# myWatch.net
KiCad netlist of a schematic drawn in EAGLE
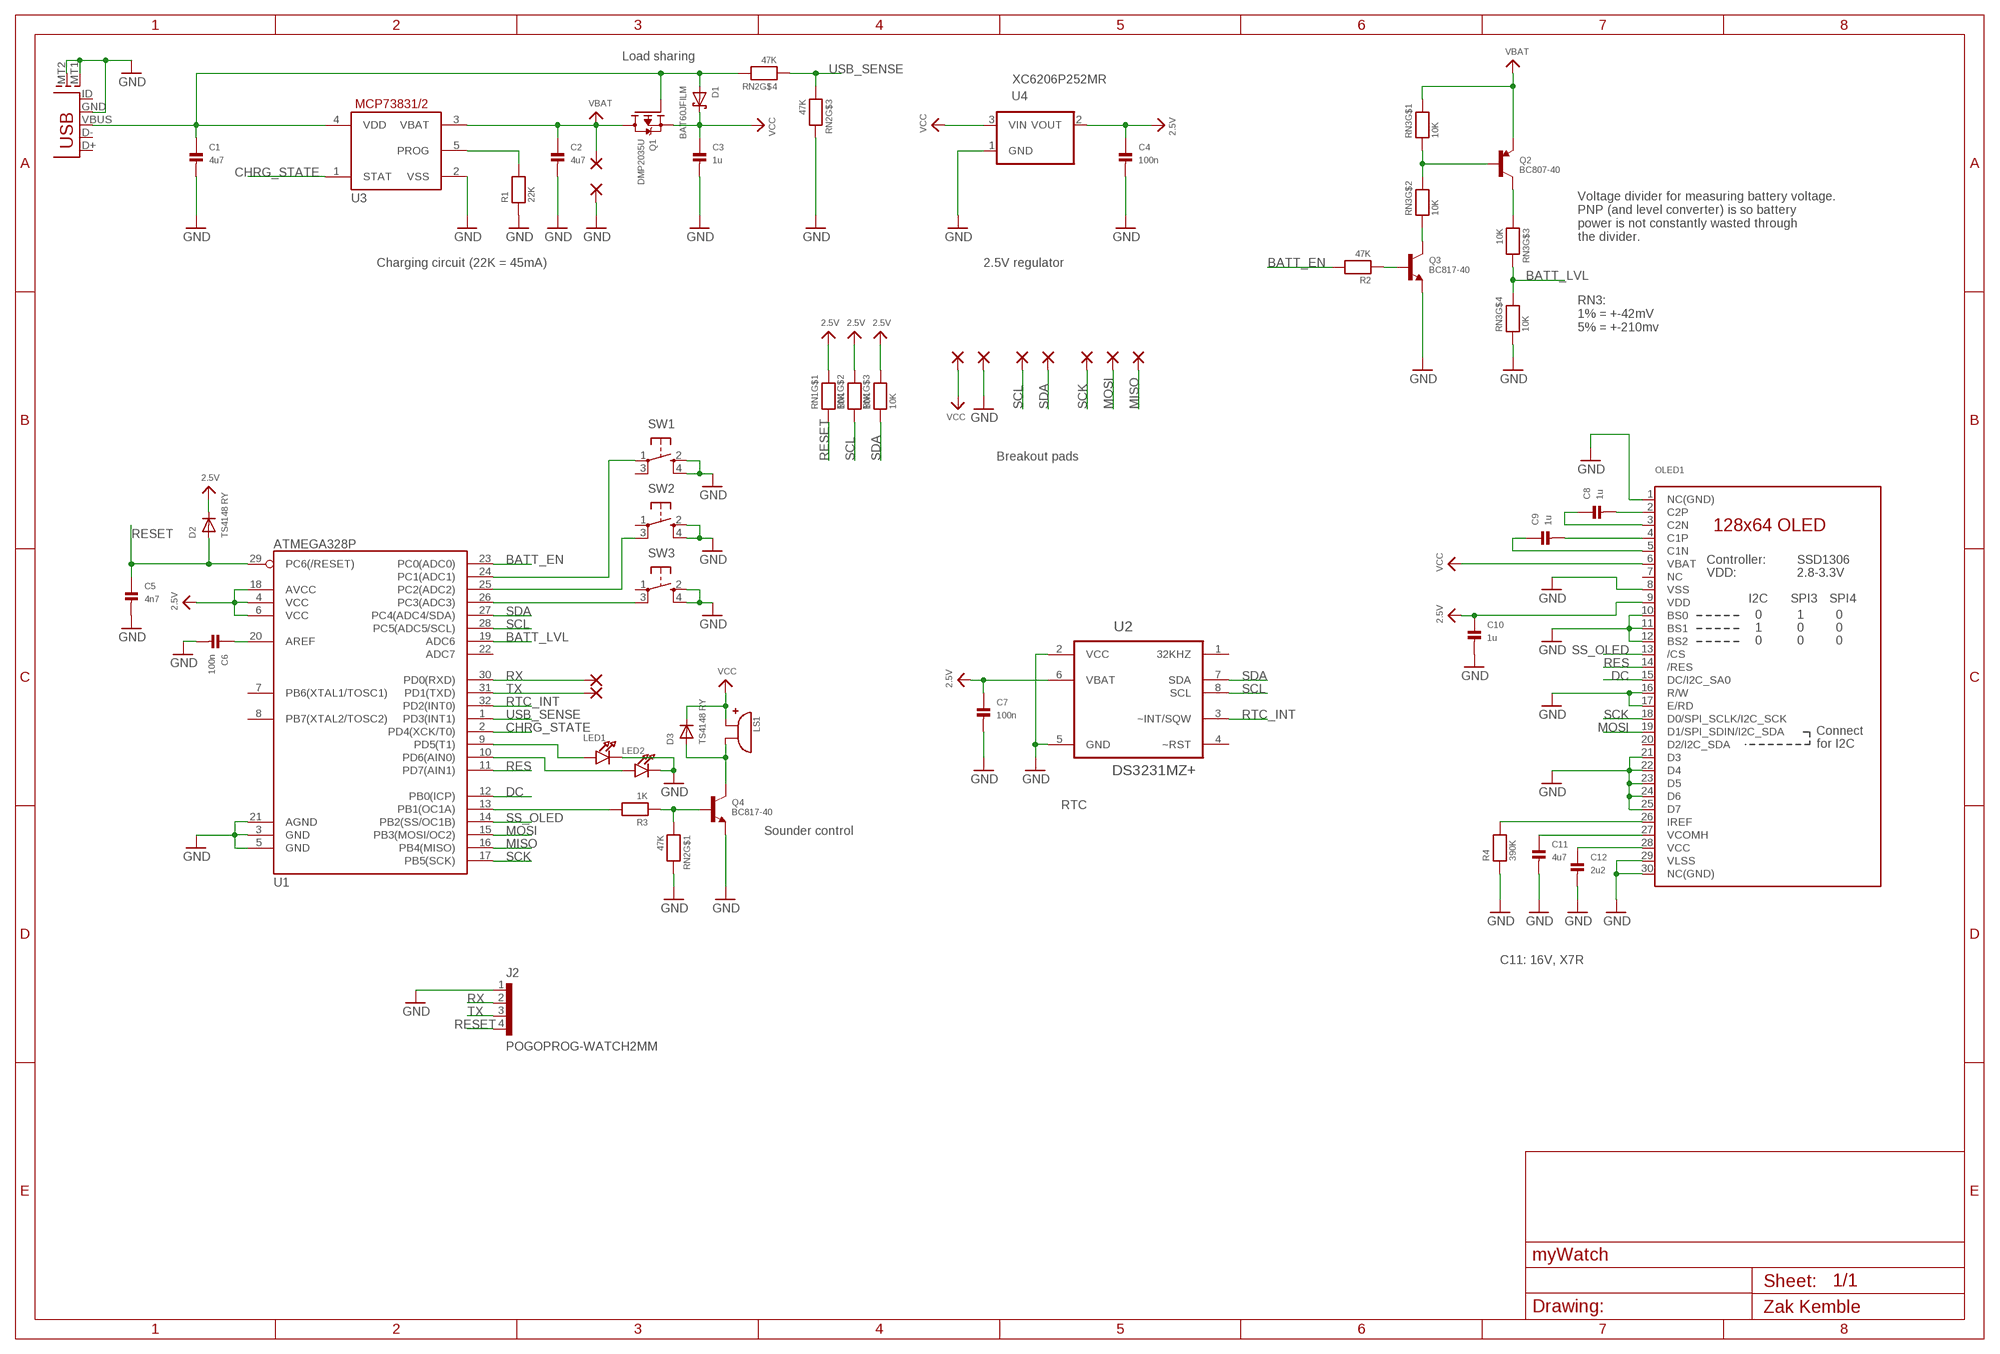
[diagram p0: schematic, sheet 1]

(export (version "E")
  (design (tool "Eeschema 10.0.6"))
  (components
    (comp (ref "C1")
      (value "4u7")
      (footprint "eagle-import:0805")
      (libsource (lib "eagle-import") (part "CAP_CERAMIC0805"))
    )
    (comp (ref "C2")
      (value "4u7")
      (footprint "eagle-import:0805")
      (libsource (lib "eagle-import") (part "CAP_CERAMIC0805"))
    )
    (comp (ref "C3")
      (value "1u")
      (footprint "eagle-import:0805")
      (libsource (lib "eagle-import") (part "CAP_CERAMIC0805"))
    )
    (comp (ref "C4")
      (value "100n")
      (footprint "eagle-import:_0402")
      (libsource (lib "eagle-import") (part "CAP_CERAMIC_0402"))
    )
    (comp (ref "C5")
      (value "4n7")
      (footprint "eagle-import:_0402")
      (libsource (lib "eagle-import") (part "CAP_CERAMIC_0402"))
    )
    (comp (ref "C6")
      (value "100n")
      (footprint "eagle-import:_0402")
      (libsource (lib "eagle-import") (part "CAP_CERAMIC_0402"))
    )
    (comp (ref "C7")
      (value "100n")
      (footprint "eagle-import:0805")
      (libsource (lib "eagle-import") (part "CAP_CERAMIC0805"))
    )
    (comp (ref "C8")
      (value "1u")
      (footprint "eagle-import:0805")
      (libsource (lib "eagle-import") (part "CAP_CERAMIC0805"))
    )
    (comp (ref "C9")
      (value "1u")
      (footprint "eagle-import:0805")
      (libsource (lib "eagle-import") (part "CAP_CERAMIC0805"))
    )
    (comp (ref "C10")
      (value "1u")
      (footprint "eagle-import:0805")
      (libsource (lib "eagle-import") (part "CAP_CERAMIC0805"))
    )
    (comp (ref "C11")
      (value "4u7")
      (footprint "eagle-import:0805")
      (libsource (lib "eagle-import") (part "CAP_CERAMIC0805"))
    )
    (comp (ref "C12")
      (value "2u2")
      (footprint "eagle-import:0805")
      (libsource (lib "eagle-import") (part "CAP_CERAMIC0805"))
    )
    (comp (ref "D1")
      (value "BAT60JFILM")
      (footprint "eagle-import:SOD-323")
      (libsource (lib "eagle-import") (part "DIODE-SCHOTTKYSOD-323"))
    )
    (comp (ref "D2")
      (value "TS4148 RY")
      (footprint "eagle-import:0805_DIODE")
      (libsource (lib "eagle-import") (part "DIODE_08050805"))
    )
    (comp (ref "D3")
      (value "TS4148 RY")
      (footprint "eagle-import:0805_DIODE")
      (libsource (lib "eagle-import") (part "DIODE_08050805"))
    )
    (comp (ref "J2")
      (value "POGOPROG-WATCH2MM")
      (footprint "eagle-import:POGOPROG_WATCH_2MM")
      (libsource (lib "eagle-import") (part "POGOPROG-WATCH2MM"))
    )
    (comp (ref "LED1")
      (value "LED0805")
      (footprint "eagle-import:CHIPLED_0805")
      (libsource (lib "eagle-import") (part "LED0805"))
    )
    (comp (ref "LED2")
      (value "LED0805")
      (footprint "eagle-import:CHIPLED_0805")
      (libsource (lib "eagle-import") (part "LED0805"))
    )
    (comp (ref "LS1")
      (value "ABMT-801-RC")
      (footprint "eagle-import:PIEZO")
      (libsource (lib "eagle-import") (part "ABMT-801-RC"))
    )
    (comp (ref "OLED1")
      (value "DISP_OLED_UG-2864HSWEG01_NOOUTLINEWATCH")
      (footprint "eagle-import:UG-2864HSWEG01_1.3_WRAPAROUND_WATCH")
      (libsource (lib "eagle-import") (part "DISP_OLED_UG-2864HSWEG01_NOOUTLINEWATCH"))
    )
    (comp (ref "PAD1")
      (value "SMD2")
      (footprint "eagle-import:SMD1,27-2,54")
      (libsource (lib "eagle-import") (part "SMD2"))
    )
    (comp (ref "PAD2")
      (value "SMD2")
      (footprint "eagle-import:SMD1,27-2,54")
      (libsource (lib "eagle-import") (part "SMD2"))
    )
    (comp (ref "PAD3")
      (value "SMD2")
      (footprint "eagle-import:SMD1,27-2,54")
      (libsource (lib "eagle-import") (part "SMD2"))
    )
    (comp (ref "PAD4")
      (value "SMD2")
      (footprint "eagle-import:SMD1,27-2,54")
      (libsource (lib "eagle-import") (part "SMD2"))
    )
    (comp (ref "PAD5")
      (value "SMD2")
      (footprint "eagle-import:SMD1,27-2,54")
      (libsource (lib "eagle-import") (part "SMD2"))
    )
    (comp (ref "PAD6")
      (value "SMD2")
      (footprint "eagle-import:SMD1,27-2,54")
      (libsource (lib "eagle-import") (part "SMD2"))
    )
    (comp (ref "PAD7")
      (value "SMD2")
      (footprint "eagle-import:SMD1,27-2,54")
      (libsource (lib "eagle-import") (part "SMD2"))
    )
    (comp (ref "PAD8")
      (value "SMD2")
      (footprint "eagle-import:SMD1,27-2,54")
      (libsource (lib "eagle-import") (part "SMD2"))
    )
    (comp (ref "PAD10")
      (value "SMD2")
      (footprint "eagle-import:SMD1,27-2,54")
      (libsource (lib "eagle-import") (part "SMD2"))
    )
    (comp (ref "PAD11")
      (value "SMD2")
      (footprint "eagle-import:SMD1,27-2,54")
      (libsource (lib "eagle-import") (part "SMD2"))
    )
    (comp (ref "PAD12")
      (value "SMD2")
      (footprint "eagle-import:SMD1,27-2,54")
      (libsource (lib "eagle-import") (part "SMD2"))
    )
    (comp (ref "Q1")
      (value "DMP2035U")
      (footprint "eagle-import:SOT23-WIDE")
      (libsource (lib "eagle-import") (part "MOSFET-PWIDE"))
    )
    (comp (ref "Q2")
      (value "BC807-40")
      (footprint "eagle-import:SOT23-WIDE")
      (libsource (lib "eagle-import") (part "TRANSISTOR_PNPWIDE"))
    )
    (comp (ref "Q3")
      (value "BC817-40")
      (footprint "eagle-import:SOT23-WIDE")
      (libsource (lib "eagle-import") (part "TRANSISTOR_NPNWIDE"))
    )
    (comp (ref "Q4")
      (value "BC817-40")
      (footprint "eagle-import:SOT23-WIDE")
      (libsource (lib "eagle-import") (part "TRANSISTOR_NPNWIDE"))
    )
    (comp (ref "R1")
      (value "22K")
      (footprint "eagle-import:_0402")
      (libsource (lib "eagle-import") (part "RESISTOR_0402"))
    )
    (comp (ref "R2")
      (value "47K")
      (footprint "eagle-import:_0402")
      (libsource (lib "eagle-import") (part "RESISTOR_0402"))
    )
    (comp (ref "R3")
      (value "1K")
      (footprint "eagle-import:_0402")
      (libsource (lib "eagle-import") (part "RESISTOR_0402"))
    )
    (comp (ref "R4")
      (value "390K")
      (footprint "eagle-import:0805")
      (libsource (lib "eagle-import") (part "RESISTOR0805"))
    )
    (comp (ref "RN1")
      (value "10K")
      (footprint "eagle-import:RESPACK_4X0603")
      (libsource (lib "eagle-import") (part "RESISTOR_4PACK"))
    )
    (comp (ref "RN2")
      (value "47K")
      (footprint "eagle-import:RESPACK_4X0603")
      (libsource (lib "eagle-import") (part "RESISTOR_4PACK"))
    )
    (comp (ref "RN3")
      (value "10K")
      (footprint "eagle-import:RESPACK_4X0603")
      (libsource (lib "eagle-import") (part "RESISTOR_4PACK"))
    )
    (comp (ref "SW1")
      (value "SPST_TACTRA")
      (footprint "eagle-import:TACT_SMD2")
      (libsource (lib "eagle-import") (part "SPST_TACTRA"))
    )
    (comp (ref "SW2")
      (value "SPST_TACTRA")
      (footprint "eagle-import:TACT_SMD2")
      (libsource (lib "eagle-import") (part "SPST_TACTRA"))
    )
    (comp (ref "SW3")
      (value "SPST_TACTRA")
      (footprint "eagle-import:TACT_SMD2")
      (libsource (lib "eagle-import") (part "SPST_TACTRA"))
    )
    (comp (ref "U1")
      (value "ATMEGA328P")
      (footprint "eagle-import:TQFP32-08")
      (libsource (lib "eagle-import") (part "ATMEGA328_SMT"))
    )
    (comp (ref "U2")
      (value "DS3231MZ+")
      (footprint "eagle-import:SOIC8_150MIL_SMPAD")
      (libsource (lib "eagle-import") (part "DS3231MZ+SMPAD"))
    )
    (comp (ref "U3")
      (value "MCP73832T-2ACI/OT")
      (footprint "eagle-import:SOT23-5L")
      (libsource (lib "eagle-import") (part "MCP73831/OT"))
    )
    (comp (ref "U4")
      (value "XC6206P252MR")
      (footprint "eagle-import:SOT-23")
      (libsource (lib "eagle-import") (part "MCP1700T-2502E/TTWIDE_PAD"))
    )
    (comp (ref "USB1")
      (value "USB-MICROBLARGEPAD")
      (footprint "eagle-import:USB-MICROB_LARGEPAD")
      (libsource (lib "eagle-import") (part "USB-MICROBLARGEPAD"))
    )
  )
  (nets
    (net (code "1") (name "/BATT_EN") (class "Default")
      (node (ref "R2") (pin "2") (pinfunction "2_2") (pintype "passive"))
      (node (ref "U1") (pin "23") (pinfunction "PC0(ADC0)_23") (pintype "bidirectional"))
    )
    (net (code "2") (name "/BATT_LVL") (class "Default")
      (node (ref "RN3") (pin "5") (pinfunction "2_5") (pintype "passive"))
      (node (ref "RN3") (pin "6") (pinfunction "2_6") (pintype "passive"))
      (node (ref "U1") (pin "19") (pinfunction "ADC6_19") (pintype "bidirectional"))
    )
    (net (code "3") (name "/CHRG_STATE") (class "Default")
      (node (ref "U1") (pin "2") (pinfunction "PD4(XCK/T0)_2") (pintype "bidirectional"))
      (node (ref "U3") (pin "1") (pinfunction "STAT_1") (pintype "output"))
    )
    (net (code "4") (name "/DC") (class "Default")
      (node (ref "OLED1") (pin "15") (pinfunction "DC/I2C_SA0_15") (pintype "input"))
      (node (ref "U1") (pin "12") (pinfunction "PB0(ICP)_12") (pintype "bidirectional"))
    )
    (net (code "5") (name "/MISO") (class "Default")
      (node (ref "PAD12") (pin "1") (pinfunction "P_1") (pintype "passive"))
      (node (ref "U1") (pin "16") (pinfunction "PB4(MISO)_16") (pintype "bidirectional"))
    )
    (net (code "6") (name "/MOSI") (class "Default")
      (node (ref "OLED1") (pin "19") (pinfunction "D1/SPI_SDIN/I2C_SDA_19") (pintype "bidirectional"))
      (node (ref "PAD11") (pin "1") (pinfunction "P_1") (pintype "passive"))
      (node (ref "U1") (pin "15") (pinfunction "PB3(MOSI/OC2)_15") (pintype "bidirectional"))
    )
    (net (code "7") (name "/RES") (class "Default")
      (node (ref "OLED1") (pin "14") (pinfunction "/RES_14") (pintype "input"))
      (node (ref "U1") (pin "11") (pinfunction "PD7(AIN1)_11") (pintype "bidirectional"))
    )
    (net (code "8") (name "/RESET") (class "Default")
      (node (ref "C5") (pin "1") (pinfunction "P$1_1") (pintype "passive"))
      (node (ref "D2") (pin "1") (pinfunction "A_1") (pintype "passive"))
      (node (ref "J2") (pin "4") (pinfunction "4_4") (pintype "bidirectional"))
      (node (ref "RN1") (pin "1") (pinfunction "1_1") (pintype "passive"))
      (node (ref "U1") (pin "29") (pinfunction "PC6(/RESET)_29") (pintype "bidirectional"))
    )
    (net (code "9") (name "/RTC_INT") (class "Default")
      (node (ref "U1") (pin "32") (pinfunction "PD2(INT0)_32") (pintype "bidirectional"))
      (node (ref "U2") (pin "3") (pinfunction "~{INT/SQW}_3") (pintype "output"))
    )
    (net (code "10") (name "/RX") (class "Default")
      (node (ref "J2") (pin "2") (pinfunction "2_2") (pintype "bidirectional"))
      (node (ref "PAD3") (pin "1") (pinfunction "P_1") (pintype "passive"))
      (node (ref "U1") (pin "30") (pinfunction "PD0(RXD)_30") (pintype "bidirectional"))
    )
    (net (code "11") (name "/SCK") (class "Default")
      (node (ref "OLED1") (pin "18") (pinfunction "D0/SPI_SCLK/I2C_SCK_18") (pintype "bidirectional"))
      (node (ref "PAD10") (pin "1") (pinfunction "P_1") (pintype "passive"))
      (node (ref "U1") (pin "17") (pinfunction "PB5(SCK)_17") (pintype "bidirectional"))
    )
    (net (code "12") (name "/SCL") (class "Default")
      (node (ref "PAD8") (pin "1") (pinfunction "P_1") (pintype "passive"))
      (node (ref "RN1") (pin "2") (pinfunction "1_2") (pintype "passive"))
      (node (ref "U1") (pin "28") (pinfunction "PC5(ADC5/SCL)_28") (pintype "bidirectional"))
      (node (ref "U2") (pin "8") (pinfunction "SCL_8") (pintype "input"))
    )
    (net (code "13") (name "/SDA") (class "Default")
      (node (ref "PAD7") (pin "1") (pinfunction "P_1") (pintype "passive"))
      (node (ref "RN1") (pin "3") (pinfunction "1_3") (pintype "passive"))
      (node (ref "U1") (pin "27") (pinfunction "PC4(ADC4/SDA)_27") (pintype "bidirectional"))
      (node (ref "U2") (pin "7") (pinfunction "SDA_7") (pintype "bidirectional"))
    )
    (net (code "14") (name "/SS_OLED") (class "Default")
      (node (ref "OLED1") (pin "13") (pinfunction "/CS_13") (pintype "input"))
      (node (ref "U1") (pin "14") (pinfunction "PB2(SS/OC1B)_14") (pintype "bidirectional"))
    )
    (net (code "15") (name "/TX") (class "Default")
      (node (ref "J2") (pin "3") (pinfunction "3_3") (pintype "bidirectional"))
      (node (ref "PAD4") (pin "1") (pinfunction "P_1") (pintype "passive"))
      (node (ref "U1") (pin "31") (pinfunction "PD1(TXD)_31") (pintype "bidirectional"))
    )
    (net (code "16") (name "/USB_SENSE") (class "Default")
      (node (ref "RN2") (pin "3") (pinfunction "1_3") (pintype "passive"))
      (node (ref "RN2") (pin "4") (pinfunction "1_4") (pintype "passive"))
      (node (ref "U1") (pin "1") (pinfunction "PD3(INT1)_1") (pintype "bidirectional"))
    )
    (net (code "17") (name "2.5V") (class "Default")
      (node (ref "C10") (pin "1") (pinfunction "P$1_1") (pintype "passive"))
      (node (ref "C4") (pin "1") (pinfunction "P$1_1") (pintype "passive"))
      (node (ref "C7") (pin "1") (pinfunction "P$1_1") (pintype "passive"))
      (node (ref "D2") (pin "2") (pinfunction "C_2") (pintype "passive"))
      (node (ref "OLED1") (pin "9") (pinfunction "VDD_9") (pintype "power_in"))
      (node (ref "RN1") (pin "6") (pinfunction "2_6") (pintype "passive"))
      (node (ref "RN1") (pin "7") (pinfunction "2_7") (pintype "passive"))
      (node (ref "RN1") (pin "8") (pinfunction "2_8") (pintype "passive"))
      (node (ref "U1") (pin "18") (pinfunction "AVCC_18") (pintype "bidirectional"))
      (node (ref "U1") (pin "4") (pinfunction "VCC_4") (pintype "bidirectional"))
      (node (ref "U1") (pin "6") (pinfunction "VCC_6") (pintype "bidirectional"))
      (node (ref "U2") (pin "6") (pinfunction "VBAT_6") (pintype "power_in"))
      (node (ref "U4") (pin "2") (pinfunction "VOUT_2") (pintype "output"))
    )
    (net (code "18") (name "GND") (class "Default")
      (node (ref "C1") (pin "2") (pinfunction "P$2_2") (pintype "passive"))
      (node (ref "C10") (pin "2") (pinfunction "P$2_2") (pintype "passive"))
      (node (ref "C11") (pin "2") (pinfunction "P$2_2") (pintype "passive"))
      (node (ref "C12") (pin "2") (pinfunction "P$2_2") (pintype "passive"))
      (node (ref "C2") (pin "2") (pinfunction "P$2_2") (pintype "passive"))
      (node (ref "C3") (pin "2") (pinfunction "P$2_2") (pintype "passive"))
      (node (ref "C4") (pin "2") (pinfunction "P$2_2") (pintype "passive"))
      (node (ref "C5") (pin "2") (pinfunction "P$2_2") (pintype "passive"))
      (node (ref "C6") (pin "2") (pinfunction "P$2_2") (pintype "passive"))
      (node (ref "C7") (pin "2") (pinfunction "P$2_2") (pintype "passive"))
      (node (ref "J2") (pin "1") (pinfunction "1_1") (pintype "bidirectional"))
      (node (ref "LED1") (pin "C") (pinfunction "C_C") (pintype "passive"))
      (node (ref "LED2") (pin "C") (pinfunction "C_C") (pintype "passive"))
      (node (ref "OLED1") (pin "1") (pinfunction "NC(GND)_1") (pintype "input"))
      (node (ref "OLED1") (pin "10") (pinfunction "BS0_10") (pintype "input"))
      (node (ref "OLED1") (pin "11") (pinfunction "BS1_11") (pintype "input"))
      (node (ref "OLED1") (pin "12") (pinfunction "BS2_12") (pintype "input"))
      (node (ref "OLED1") (pin "16") (pinfunction "R/W_16") (pintype "input"))
      (node (ref "OLED1") (pin "17") (pinfunction "E/RD_17") (pintype "input"))
      (node (ref "OLED1") (pin "21") (pinfunction "D3_21") (pintype "bidirectional"))
      (node (ref "OLED1") (pin "22") (pinfunction "D4_22") (pintype "bidirectional"))
      (node (ref "OLED1") (pin "23") (pinfunction "D5_23") (pintype "bidirectional"))
      (node (ref "OLED1") (pin "24") (pinfunction "D6_24") (pintype "bidirectional"))
      (node (ref "OLED1") (pin "25") (pinfunction "D7_25") (pintype "bidirectional"))
      (node (ref "OLED1") (pin "29") (pinfunction "VLSS_29") (pintype "power_in"))
      (node (ref "OLED1") (pin "30") (pinfunction "NC(GND)_30") (pintype "input"))
      (node (ref "OLED1") (pin "8") (pinfunction "VSS_8") (pintype "power_in"))
      (node (ref "PAD2") (pin "1") (pinfunction "P_1") (pintype "passive"))
      (node (ref "PAD5") (pin "1") (pinfunction "P_1") (pintype "passive"))
      (node (ref "Q3") (pin "2") (pinfunction "E_2") (pintype "passive"))
      (node (ref "Q4") (pin "2") (pinfunction "E_2") (pintype "passive"))
      (node (ref "R1") (pin "1") (pinfunction "1_1") (pintype "passive"))
      (node (ref "R4") (pin "1") (pinfunction "1_1") (pintype "passive"))
      (node (ref "RN2") (pin "6") (pinfunction "2_6") (pintype "passive"))
      (node (ref "RN2") (pin "8") (pinfunction "2_8") (pintype "passive"))
      (node (ref "RN3") (pin "4") (pinfunction "1_4") (pintype "passive"))
      (node (ref "SW1") (pin "2") (pinfunction "S_2") (pintype "passive"))
      (node (ref "SW1") (pin "4") (pinfunction "S1_4") (pintype "passive"))
      (node (ref "SW2") (pin "2") (pinfunction "S_2") (pintype "passive"))
      (node (ref "SW2") (pin "4") (pinfunction "S1_4") (pintype "passive"))
      (node (ref "SW3") (pin "2") (pinfunction "S_2") (pintype "passive"))
      (node (ref "SW3") (pin "4") (pinfunction "S1_4") (pintype "passive"))
      (node (ref "U1") (pin "21") (pinfunction "AGND_21") (pintype "bidirectional"))
      (node (ref "U1") (pin "3") (pinfunction "GND_3") (pintype "bidirectional"))
      (node (ref "U1") (pin "5") (pinfunction "GND_5") (pintype "bidirectional"))
      (node (ref "U2") (pin "2") (pinfunction "VCC_2") (pintype "power_in"))
      (node (ref "U2") (pin "5") (pinfunction "GND_5") (pintype "passive"))
      (node (ref "U3") (pin "2") (pinfunction "VSS_2") (pintype "power_in"))
      (node (ref "U4") (pin "1") (pinfunction "GND_1") (pintype "passive"))
      (node (ref "USB1") (pin "GND") (pinfunction "GND_GND") (pintype "bidirectional"))
      (node (ref "USB1") (pin "MT1") (pinfunction "SHEILD1_MT1") (pintype "bidirectional"))
      (node (ref "USB1") (pin "MT2") (pinfunction "SHEILD2_MT2") (pintype "bidirectional"))
    )
    (net (code "19") (name "Net-(C1-P$1)") (class "Default")
      (node (ref "C1") (pin "1") (pinfunction "P$1_1") (pintype "passive"))
      (node (ref "D1") (pin "A") (pinfunction "A_A") (pintype "passive"))
      (node (ref "Q1") (pin "1") (pinfunction "G_1") (pintype "passive"))
      (node (ref "RN2") (pin "5") (pinfunction "2_5") (pintype "passive"))
      (node (ref "U3") (pin "4") (pinfunction "VDD_4") (pintype "power_in"))
      (node (ref "USB1") (pin "VBUS") (pinfunction "VBUS_VBUS") (pintype "bidirectional"))
    )
    (net (code "20") (name "Net-(C6-P$1)") (class "Default")
      (node (ref "C6") (pin "1") (pinfunction "P$1_1") (pintype "passive"))
      (node (ref "U1") (pin "20") (pinfunction "AREF_20") (pintype "bidirectional"))
    )
    (net (code "21") (name "Net-(C8-P$1)") (class "Default")
      (node (ref "C8") (pin "1") (pinfunction "P$1_1") (pintype "passive"))
      (node (ref "OLED1") (pin "3") (pinfunction "C2N_3") (pintype "input"))
    )
    (net (code "22") (name "Net-(C8-P$2)") (class "Default")
      (node (ref "C8") (pin "2") (pinfunction "P$2_2") (pintype "passive"))
      (node (ref "OLED1") (pin "2") (pinfunction "C2P_2") (pintype "input"))
    )
    (net (code "23") (name "Net-(C9-P$1)") (class "Default")
      (node (ref "C9") (pin "1") (pinfunction "P$1_1") (pintype "passive"))
      (node (ref "OLED1") (pin "5") (pinfunction "C1N_5") (pintype "input"))
    )
    (net (code "24") (name "Net-(C9-P$2)") (class "Default")
      (node (ref "C9") (pin "2") (pinfunction "P$2_2") (pintype "passive"))
      (node (ref "OLED1") (pin "4") (pinfunction "C1P_4") (pintype "input"))
    )
    (net (code "25") (name "Net-(C11-P$1)") (class "Default")
      (node (ref "C11") (pin "1") (pinfunction "P$1_1") (pintype "passive"))
      (node (ref "OLED1") (pin "27") (pinfunction "VCOMH_27") (pintype "output"))
    )
    (net (code "26") (name "Net-(C12-P$1)") (class "Default")
      (node (ref "C12") (pin "1") (pinfunction "P$1_1") (pintype "passive"))
      (node (ref "OLED1") (pin "28") (pinfunction "VCC_28") (pintype "power_in"))
    )
    (net (code "27") (name "Net-(D3-A)") (class "Default")
      (node (ref "D3") (pin "1") (pinfunction "A_1") (pintype "passive"))
      (node (ref "LS1") (pin "2") (pinfunction "GND_2") (pintype "passive"))
      (node (ref "Q4") (pin "3") (pinfunction "C_3") (pintype "passive"))
    )
    (net (code "28") (name "Net-(OLED1-IREF)") (class "Default")
      (node (ref "OLED1") (pin "26") (pinfunction "IREF_26") (pintype "input"))
      (node (ref "R4") (pin "2") (pinfunction "2_2") (pintype "passive"))
    )
    (net (code "29") (name "Net-(Q2-B)") (class "Default")
      (node (ref "Q2") (pin "1") (pinfunction "B_1") (pintype "passive"))
      (node (ref "RN3") (pin "1") (pinfunction "1_1") (pintype "passive"))
      (node (ref "RN3") (pin "7") (pinfunction "2_7") (pintype "passive"))
    )
    (net (code "30") (name "Net-(Q2-C)") (class "Default")
      (node (ref "Q2") (pin "3") (pinfunction "C_3") (pintype "passive"))
      (node (ref "RN3") (pin "3") (pinfunction "1_3") (pintype "passive"))
    )
    (net (code "31") (name "Net-(Q3-B)") (class "Default")
      (node (ref "Q3") (pin "1") (pinfunction "B_1") (pintype "passive"))
      (node (ref "R2") (pin "1") (pinfunction "1_1") (pintype "passive"))
    )
    (net (code "32") (name "Net-(Q3-C)") (class "Default")
      (node (ref "Q3") (pin "3") (pinfunction "C_3") (pintype "passive"))
      (node (ref "RN3") (pin "2") (pinfunction "1_2") (pintype "passive"))
    )
    (net (code "33") (name "Net-(Q4-B)") (class "Default")
      (node (ref "Q4") (pin "1") (pinfunction "B_1") (pintype "passive"))
      (node (ref "R3") (pin "1") (pinfunction "1_1") (pintype "passive"))
      (node (ref "RN2") (pin "1") (pinfunction "1_1") (pintype "passive"))
    )
    (net (code "34") (name "Net-(SW1-P)") (class "Default")
      (node (ref "SW1") (pin "1") (pinfunction "P_1") (pintype "passive"))
      (node (ref "U1") (pin "24") (pinfunction "PC1(ADC1)_24") (pintype "bidirectional"))
    )
    (net (code "35") (name "Net-(SW2-P1)") (class "Default")
      (node (ref "SW2") (pin "3") (pinfunction "P1_3") (pintype "passive"))
      (node (ref "U1") (pin "25") (pinfunction "PC2(ADC2)_25") (pintype "bidirectional"))
    )
    (net (code "36") (name "Net-(SW3-P1)") (class "Default")
      (node (ref "SW3") (pin "3") (pinfunction "P1_3") (pintype "passive"))
      (node (ref "U1") (pin "26") (pinfunction "PC3(ADC3)_26") (pintype "bidirectional"))
    )
    (net (code "37") (name "Net-(U1-PB1(OC1A))") (class "Default")
      (node (ref "R3") (pin "2") (pinfunction "2_2") (pintype "passive"))
      (node (ref "U1") (pin "13") (pinfunction "PB1(OC1A)_13") (pintype "bidirectional"))
    )
    (net (code "38") (name "Net-(U1-PD5(T1))") (class "Default")
      (node (ref "LED1") (pin "A") (pinfunction "A_A") (pintype "passive"))
      (node (ref "U1") (pin "9") (pinfunction "PD5(T1)_9") (pintype "bidirectional"))
    )
    (net (code "39") (name "Net-(U1-PD6(AIN0))") (class "Default")
      (node (ref "LED2") (pin "A") (pinfunction "A_A") (pintype "passive"))
      (node (ref "U1") (pin "10") (pinfunction "PD6(AIN0)_10") (pintype "bidirectional"))
    )
    (net (code "40") (name "Net-(U3-PROG)") (class "Default")
      (node (ref "R1") (pin "2") (pinfunction "2_2") (pintype "passive"))
      (node (ref "U3") (pin "5") (pinfunction "PROG_5") (pintype "input"))
    )
    (net (code "41") (name "VBAT") (class "Default")
      (node (ref "C2") (pin "1") (pinfunction "P$1_1") (pintype "passive"))
      (node (ref "PAD1") (pin "1") (pinfunction "P_1") (pintype "passive"))
      (node (ref "Q1") (pin "3") (pinfunction "D_3") (pintype "passive"))
      (node (ref "Q2") (pin "2") (pinfunction "E_2") (pintype "passive"))
      (node (ref "RN3") (pin "8") (pinfunction "2_8") (pintype "passive"))
      (node (ref "U3") (pin "3") (pinfunction "VBAT_3") (pintype "bidirectional"))
    )
    (net (code "42") (name "VCC") (class "Default")
      (node (ref "C3") (pin "1") (pinfunction "P$1_1") (pintype "passive"))
      (node (ref "D1") (pin "C") (pinfunction "C_C") (pintype "passive"))
      (node (ref "D3") (pin "2") (pinfunction "C_2") (pintype "passive"))
      (node (ref "LS1") (pin "1") (pinfunction "VCC_1") (pintype "passive"))
      (node (ref "OLED1") (pin "6") (pinfunction "VBAT_6") (pintype "input"))
      (node (ref "PAD6") (pin "1") (pinfunction "P_1") (pintype "passive"))
      (node (ref "Q1") (pin "2") (pinfunction "S_2") (pintype "passive"))
      (node (ref "U4") (pin "3") (pinfunction "VIN_3") (pintype "power_in"))
    )
    (net (code "43") (name "unconnected-(OLED1-D2{slash}I2C_SDA-Pad20)") (class "Default")
      (node (ref "OLED1") (pin "20") (pinfunction "D2/I2C_SDA_20") (pintype "bidirectional"))
    )
    (net (code "44") (name "unconnected-(OLED1-NC-Pad7)") (class "Default")
      (node (ref "OLED1") (pin "7") (pinfunction "NC_7") (pintype "no_connect"))
    )
    (net (code "45") (name "unconnected-(SW1-P1-Pad3)") (class "Default")
      (node (ref "SW1") (pin "3") (pinfunction "P1_3") (pintype "passive"))
    )
    (net (code "46") (name "unconnected-(SW2-P-Pad1)") (class "Default")
      (node (ref "SW2") (pin "1") (pinfunction "P_1") (pintype "passive"))
    )
    (net (code "47") (name "unconnected-(SW3-P-Pad1)") (class "Default")
      (node (ref "SW3") (pin "1") (pinfunction "P_1") (pintype "passive"))
    )
    (net (code "48") (name "unconnected-(U1-ADC7-Pad22)") (class "Default")
      (node (ref "U1") (pin "22") (pinfunction "ADC7_22") (pintype "bidirectional"))
    )
    (net (code "49") (name "unconnected-(U1-PB6(XTAL1{slash}TOSC1)-Pad7)") (class "Default")
      (node (ref "U1") (pin "7") (pinfunction "PB6(XTAL1/TOSC1)_7") (pintype "bidirectional"))
    )
    (net (code "50") (name "unconnected-(U1-PB7(XTAL2{slash}TOSC2)-Pad8)") (class "Default")
      (node (ref "U1") (pin "8") (pinfunction "PB7(XTAL2/TOSC2)_8") (pintype "bidirectional"))
    )
    (net (code "51") (name "unconnected-(U2-32KHZ-Pad1)") (class "Default")
      (node (ref "U2") (pin "1") (pinfunction "32KHZ_1") (pintype "output"))
    )
    (net (code "52") (name "unconnected-(U2-~{RST}-Pad4)") (class "Default")
      (node (ref "U2") (pin "4") (pinfunction "~{RST}_4") (pintype "bidirectional"))
    )
    (net (code "53") (name "unconnected-(USB1-PadD+)") (class "Default")
      (node (ref "USB1") (pin "D+") (pinfunction "D+_D+") (pintype "bidirectional"))
    )
    (net (code "54") (name "unconnected-(USB1-PadD-)") (class "Default")
      (node (ref "USB1") (pin "D-") (pinfunction "D-_D-") (pintype "bidirectional"))
    )
    (net (code "55") (name "unconnected-(USB1-PadID)") (class "Default")
      (node (ref "USB1") (pin "ID") (pinfunction "ID_ID") (pintype "bidirectional"))
    )
  )
)
